# LIC_V-00237-02.net
KiCad netlist of a schematic drawn in EAGLE
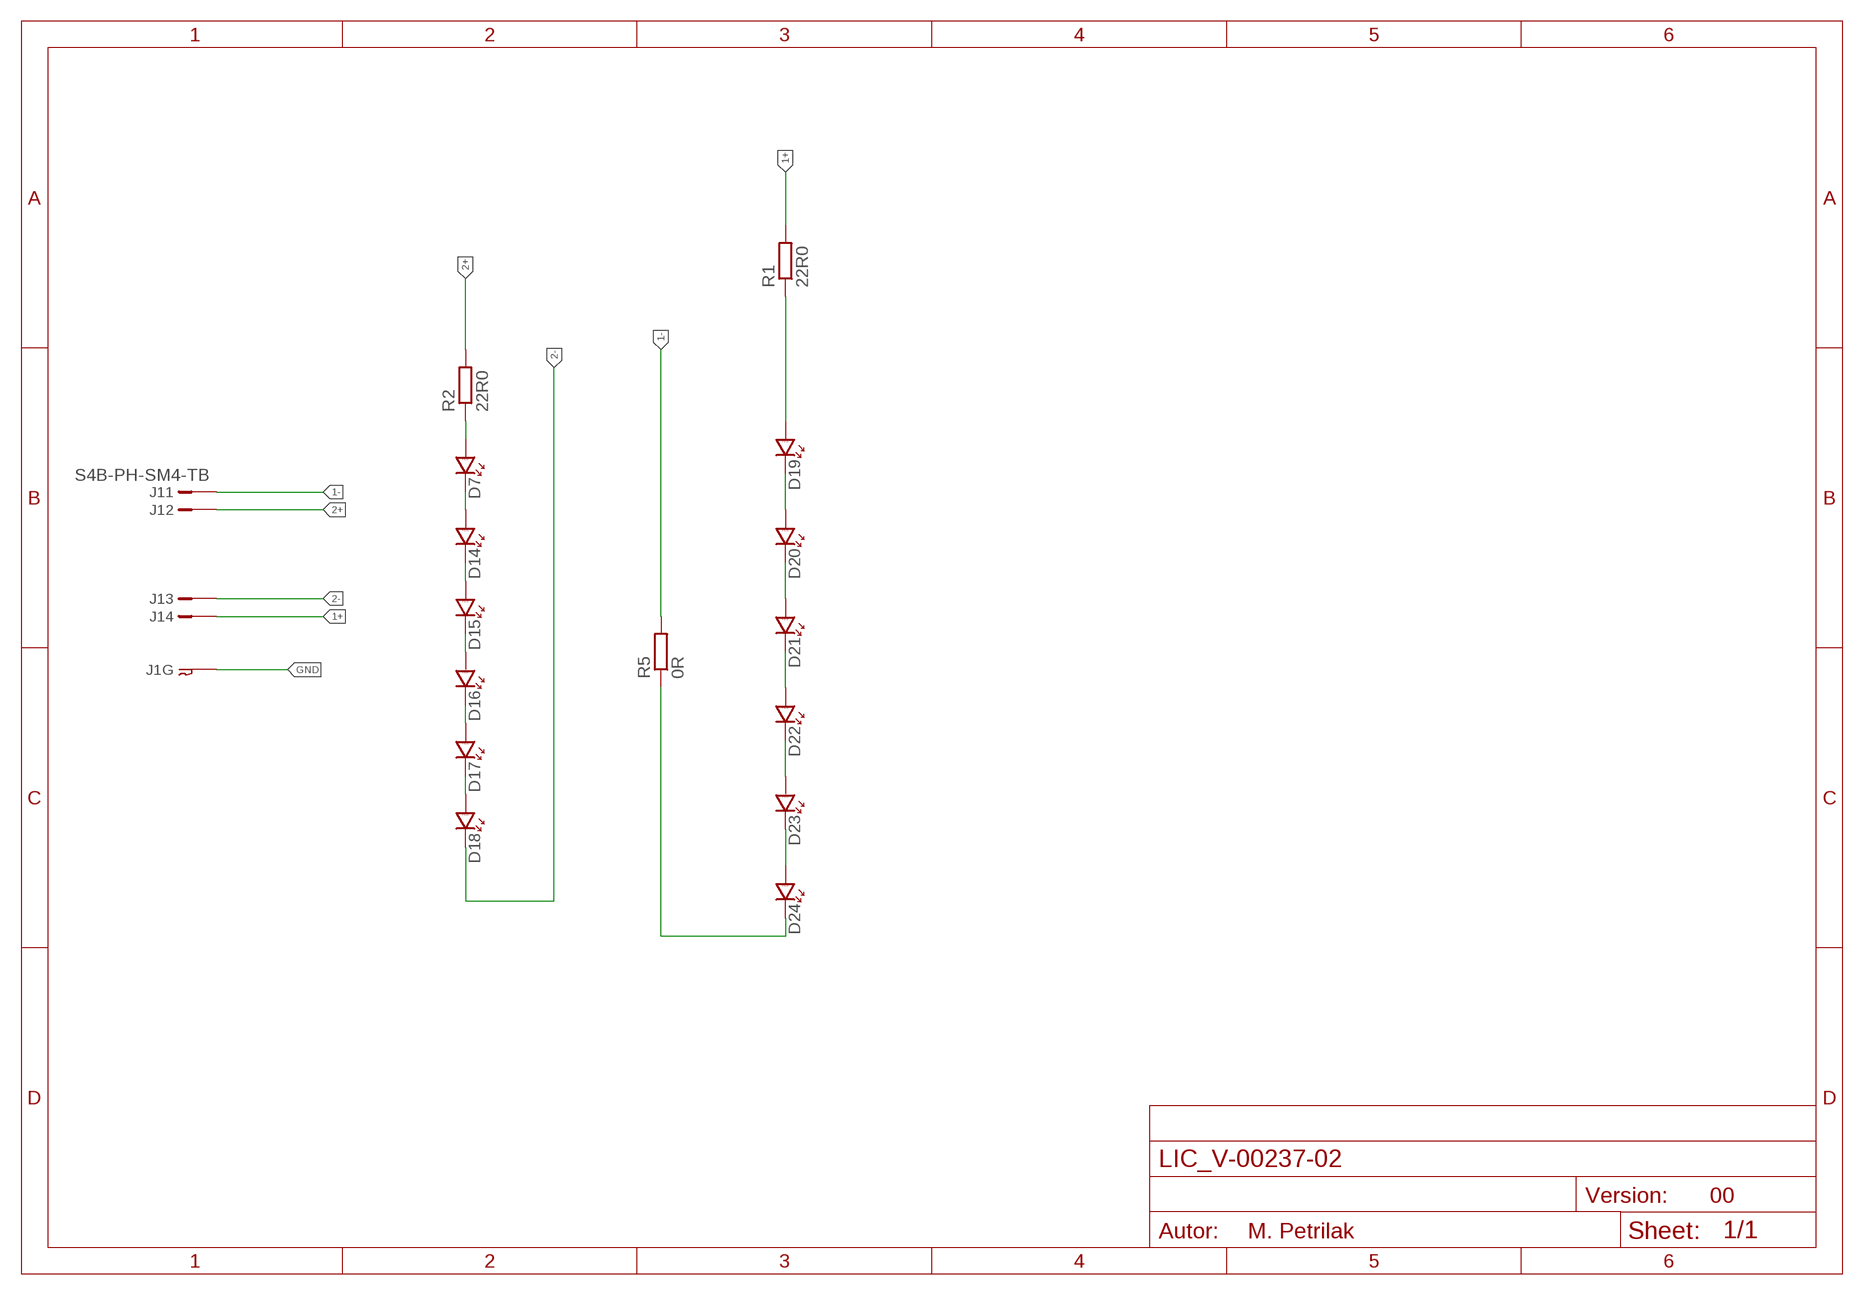
[diagram p0: schematic, sheet 1]

(export (version "E")
  (design (tool "Eeschema 10.0.6"))
  (components
    (comp (ref "D7")
      (value "LED_1206")
      (footprint "eagle-import:P1206")
      (libsource (lib "eagle-import") (part "LED_1206"))
    )
    (comp (ref "D14")
      (value "LED_1206")
      (footprint "eagle-import:P1206")
      (libsource (lib "eagle-import") (part "LED_1206"))
    )
    (comp (ref "D15")
      (value "LED_1206")
      (footprint "eagle-import:P1206")
      (libsource (lib "eagle-import") (part "LED_1206"))
    )
    (comp (ref "D16")
      (value "LED_1206")
      (footprint "eagle-import:P1206")
      (libsource (lib "eagle-import") (part "LED_1206"))
    )
    (comp (ref "D17")
      (value "LED_1206")
      (footprint "eagle-import:P1206")
      (libsource (lib "eagle-import") (part "LED_1206"))
    )
    (comp (ref "D18")
      (value "LED_1206")
      (footprint "eagle-import:P1206")
      (libsource (lib "eagle-import") (part "LED_1206"))
    )
    (comp (ref "D19")
      (value "LED_1206")
      (footprint "eagle-import:P1206")
      (libsource (lib "eagle-import") (part "LED_1206"))
    )
    (comp (ref "D20")
      (value "LED_1206")
      (footprint "eagle-import:P1206")
      (libsource (lib "eagle-import") (part "LED_1206"))
    )
    (comp (ref "D21")
      (value "LED_1206")
      (footprint "eagle-import:P1206")
      (libsource (lib "eagle-import") (part "LED_1206"))
    )
    (comp (ref "D22")
      (value "LED_1206")
      (footprint "eagle-import:P1206")
      (libsource (lib "eagle-import") (part "LED_1206"))
    )
    (comp (ref "D23")
      (value "LED_1206")
      (footprint "eagle-import:P1206")
      (libsource (lib "eagle-import") (part "LED_1206"))
    )
    (comp (ref "D24")
      (value "LED_1206")
      (footprint "eagle-import:P1206")
      (libsource (lib "eagle-import") (part "LED_1206"))
    )
    (comp (ref "J1")
      (value "S4B-PH-SM4-TB")
      (footprint "eagle-import:S4B-PH-SM4-TB")
      (libsource (lib "eagle-import") (part "?4B-PH-SM4-TBS"))
    )
    (comp (ref "R1")
      (value "22R0")
      (footprint "eagle-import:R1206")
      (libsource (lib "eagle-import") (part "R-EU_R1206"))
    )
    (comp (ref "R2")
      (value "22R0")
      (footprint "eagle-import:R1206")
      (libsource (lib "eagle-import") (part "R-EU_R1206"))
    )
    (comp (ref "R5")
      (value "0R")
      (footprint "eagle-import:R1206")
      (libsource (lib "eagle-import") (part "R-EU_R1206"))
    )
  )
  (nets
    (net (code "1") (name "1+") (class "Default")
      (node (ref "J1") (pin "4") (pinfunction "1_4") (pintype "passive"))
      (node (ref "R1") (pin "2") (pinfunction "2_2") (pintype "passive"))
    )
    (net (code "2") (name "1-") (class "Default")
      (node (ref "J1") (pin "1") (pinfunction "1_1") (pintype "passive"))
      (node (ref "R5") (pin "2") (pinfunction "2_2") (pintype "passive"))
    )
    (net (code "3") (name "2+") (class "Default")
      (node (ref "J1") (pin "2") (pinfunction "1_2") (pintype "passive"))
      (node (ref "R2") (pin "2") (pinfunction "2_2") (pintype "passive"))
    )
    (net (code "4") (name "2-") (class "Default")
      (node (ref "D18") (pin "K") (pinfunction "K_K") (pintype "passive"))
      (node (ref "J1") (pin "3") (pinfunction "1_3") (pintype "passive"))
    )
    (net (code "5") (name "GND") (class "Default")
      (node (ref "J1") (pin "GND1") (pinfunction "1_GND1") (pintype "passive"))
      (node (ref "J1") (pin "GND2") (pinfunction "1_GND2") (pintype "passive"))
    )
    (net (code "6") (name "Net-(D7-PadA)") (class "Default")
      (node (ref "D7") (pin "A") (pinfunction "A_A") (pintype "passive"))
      (node (ref "R2") (pin "1") (pinfunction "1_1") (pintype "passive"))
    )
    (net (code "7") (name "Net-(D14-PadA)") (class "Default")
      (node (ref "D14") (pin "A") (pinfunction "A_A") (pintype "passive"))
      (node (ref "D7") (pin "K") (pinfunction "K_K") (pintype "passive"))
    )
    (net (code "8") (name "Net-(D14-PadK)") (class "Default")
      (node (ref "D14") (pin "K") (pinfunction "K_K") (pintype "passive"))
      (node (ref "D15") (pin "A") (pinfunction "A_A") (pintype "passive"))
    )
    (net (code "9") (name "Net-(D15-PadK)") (class "Default")
      (node (ref "D15") (pin "K") (pinfunction "K_K") (pintype "passive"))
      (node (ref "D16") (pin "A") (pinfunction "A_A") (pintype "passive"))
    )
    (net (code "10") (name "Net-(D16-PadK)") (class "Default")
      (node (ref "D16") (pin "K") (pinfunction "K_K") (pintype "passive"))
      (node (ref "D17") (pin "A") (pinfunction "A_A") (pintype "passive"))
    )
    (net (code "11") (name "Net-(D17-PadK)") (class "Default")
      (node (ref "D17") (pin "K") (pinfunction "K_K") (pintype "passive"))
      (node (ref "D18") (pin "A") (pinfunction "A_A") (pintype "passive"))
    )
    (net (code "12") (name "Net-(D19-PadA)") (class "Default")
      (node (ref "D19") (pin "A") (pinfunction "A_A") (pintype "passive"))
      (node (ref "R1") (pin "1") (pinfunction "1_1") (pintype "passive"))
    )
    (net (code "13") (name "Net-(D19-PadK)") (class "Default")
      (node (ref "D19") (pin "K") (pinfunction "K_K") (pintype "passive"))
      (node (ref "D20") (pin "A") (pinfunction "A_A") (pintype "passive"))
    )
    (net (code "14") (name "Net-(D20-PadK)") (class "Default")
      (node (ref "D20") (pin "K") (pinfunction "K_K") (pintype "passive"))
      (node (ref "D21") (pin "A") (pinfunction "A_A") (pintype "passive"))
    )
    (net (code "15") (name "Net-(D21-PadK)") (class "Default")
      (node (ref "D21") (pin "K") (pinfunction "K_K") (pintype "passive"))
      (node (ref "D22") (pin "A") (pinfunction "A_A") (pintype "passive"))
    )
    (net (code "16") (name "Net-(D22-PadK)") (class "Default")
      (node (ref "D22") (pin "K") (pinfunction "K_K") (pintype "passive"))
      (node (ref "D23") (pin "A") (pinfunction "A_A") (pintype "passive"))
    )
    (net (code "17") (name "Net-(D23-PadK)") (class "Default")
      (node (ref "D23") (pin "K") (pinfunction "K_K") (pintype "passive"))
      (node (ref "D24") (pin "A") (pinfunction "A_A") (pintype "passive"))
    )
    (net (code "18") (name "Net-(D24-PadK)") (class "Default")
      (node (ref "D24") (pin "K") (pinfunction "K_K") (pintype "passive"))
      (node (ref "R5") (pin "1") (pinfunction "1_1") (pintype "passive"))
    )
  )
)
